# sonoff_DIY_3_gang_Smd_version-V_1_3.net
KiCad netlist of a schematic drawn in EAGLE
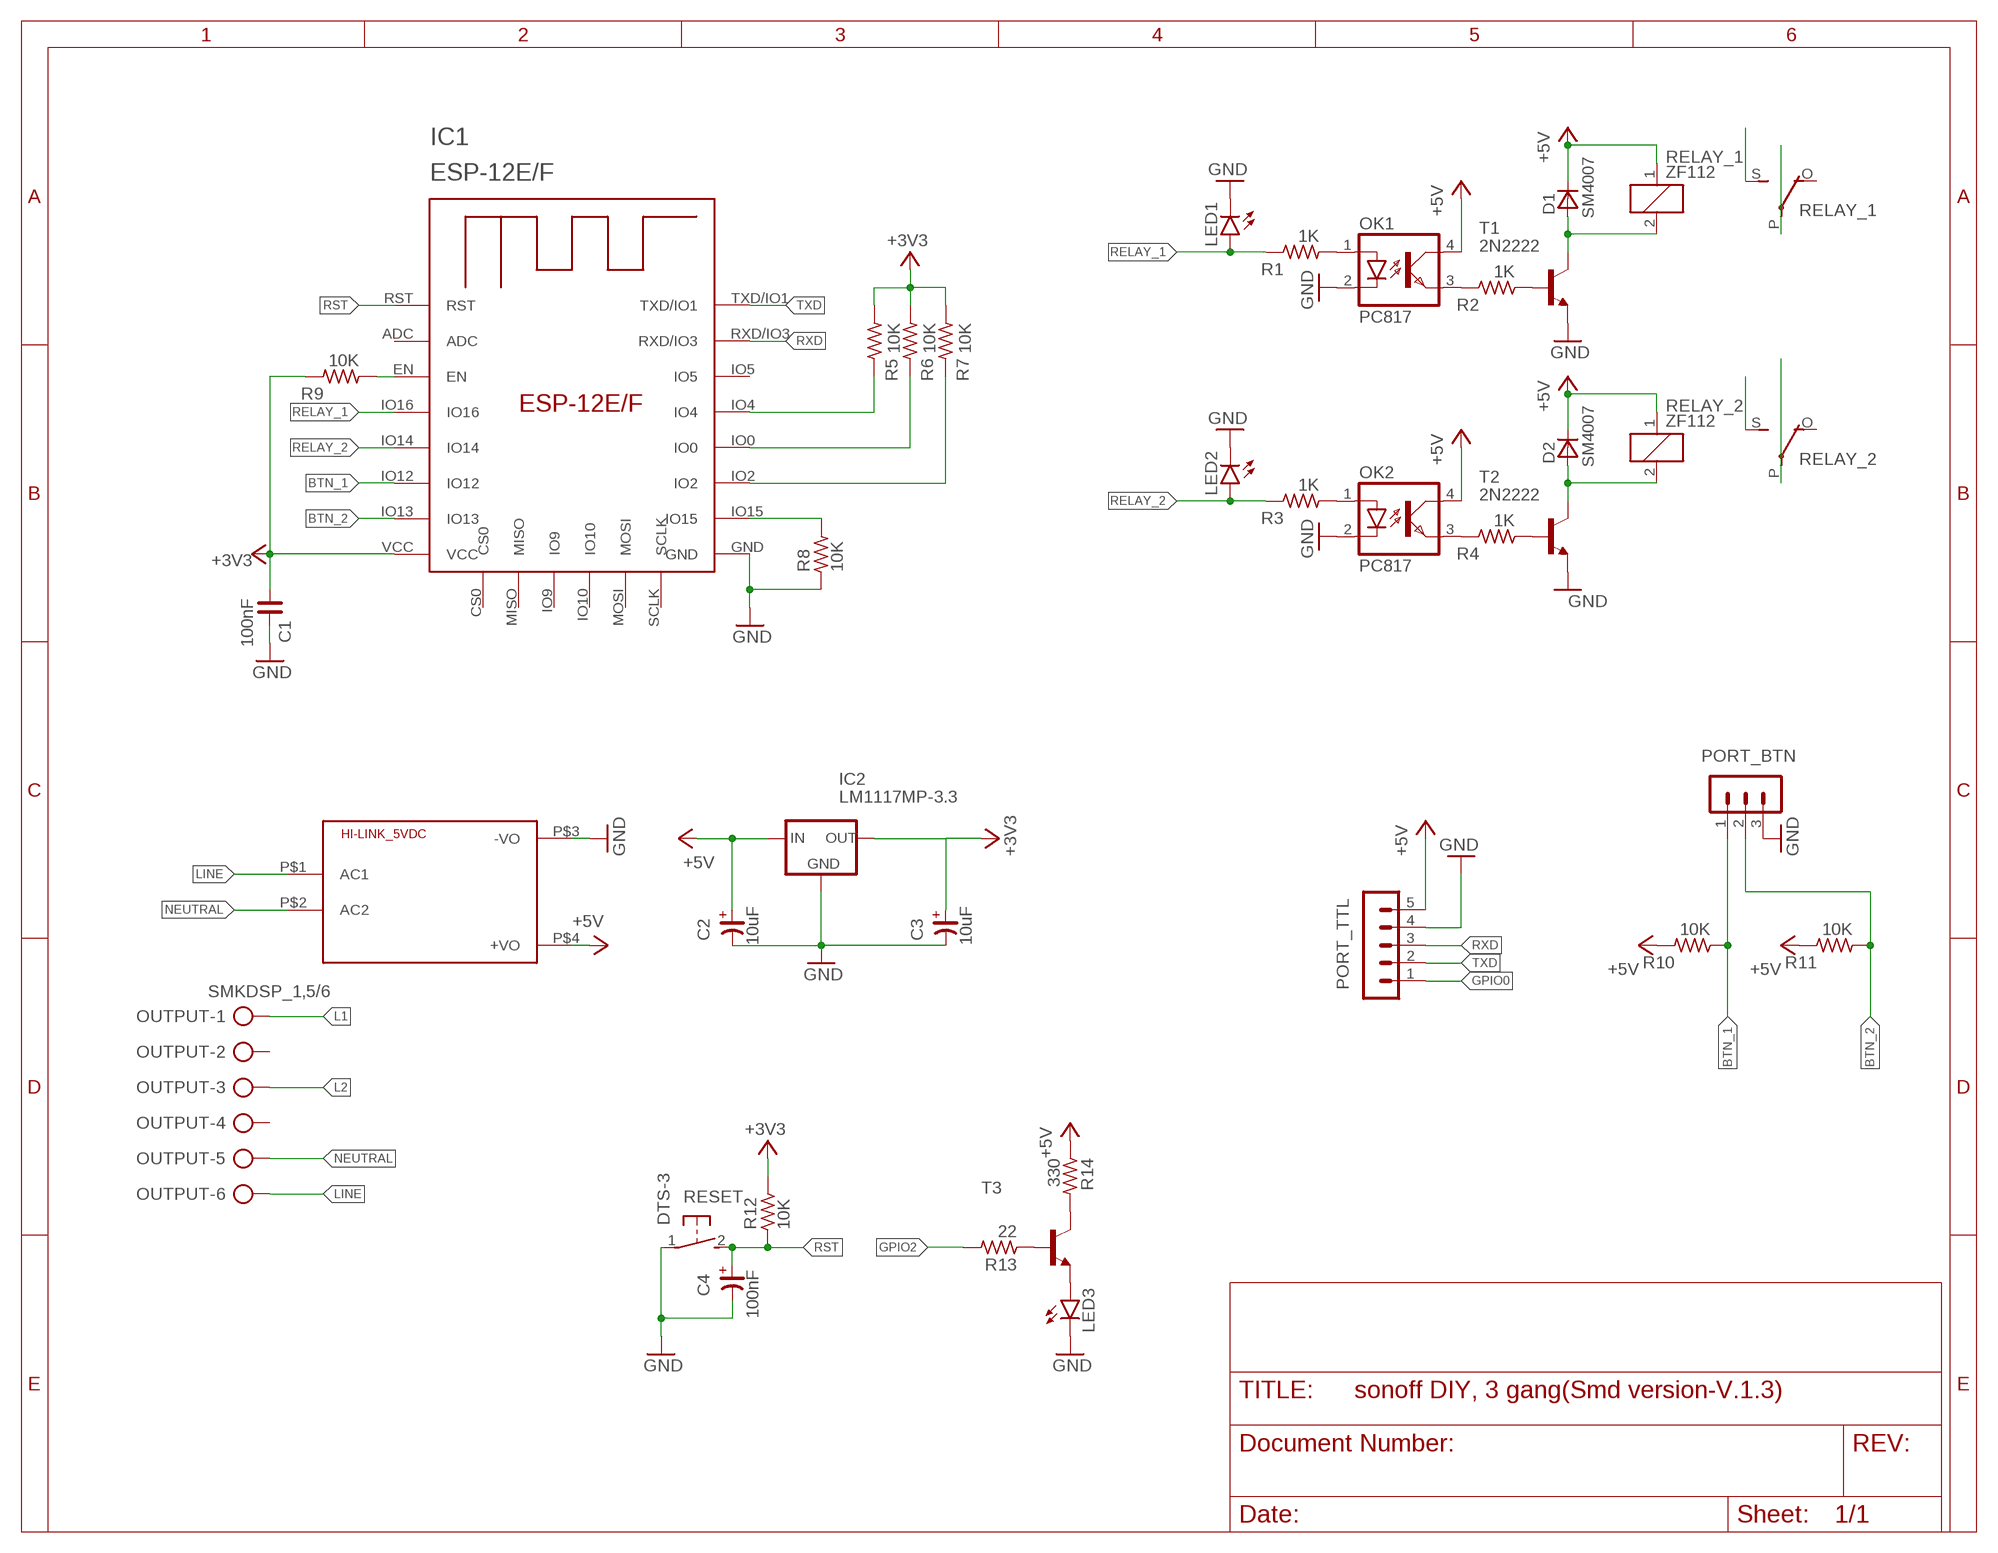
[diagram p0: schematic, sheet 1]

(export (version "E")
  (design (tool "Eeschema 10.0.6"))
  (components
    (comp (ref "C1")
      (value "100nF")
      (footprint "eagle-import:C0805")
      (libsource (lib "eagle-import") (part "C_0805"))
    )
    (comp (ref "C2")
      (value "10uF")
      (footprint "eagle-import:C3528_T")
      (libsource (lib "eagle-import") (part "CP_3528"))
    )
    (comp (ref "C3")
      (value "10uF")
      (footprint "eagle-import:C3528_T")
      (libsource (lib "eagle-import") (part "CP_3528"))
    )
    (comp (ref "C4")
      (value "100nF")
      (footprint "eagle-import:C3528_T")
      (libsource (lib "eagle-import") (part "CP_3528"))
    )
    (comp (ref "D1")
      (value "SM4007")
      (footprint "eagle-import:MELF-MLL41")
      (libsource (lib "eagle-import") (part "SM4007"))
    )
    (comp (ref "D2")
      (value "SM4007")
      (footprint "eagle-import:MELF-MLL41")
      (libsource (lib "eagle-import") (part "SM4007"))
    )
    (comp (ref "HI-LINK_5VDC")
      (value "HLK-PM013W")
      (footprint "eagle-import:HLK-PM01")
      (libsource (lib "eagle-import") (part "HLK-PM013W"))
    )
    (comp (ref "IC1")
      (value "ESP-12E/F")
      (footprint "eagle-import:ESP-12E")
      (libsource (lib "eagle-import") (part "ESP-12E/F"))
    )
    (comp (ref "IC2")
      (value "LM1117MP-3.3")
      (footprint "eagle-import:SOT223")
      (fields (field (name "MF") "Texas Instruments"))
      (libsource (lib "eagle-import") (part "LM1117?-MP3.3"))
    )
    (comp (ref "LED1")
      (value "LED3MM")
      (footprint "eagle-import:LED3MM")
      (libsource (lib "eagle-import") (part "LED3MM"))
    )
    (comp (ref "LED2")
      (value "LED3MM")
      (footprint "eagle-import:LED3MM")
      (libsource (lib "eagle-import") (part "LED3MM"))
    )
    (comp (ref "LED3")
      (value "LED3MM")
      (footprint "eagle-import:LED3MM")
      (libsource (lib "eagle-import") (part "LED3MM"))
    )
    (comp (ref "OK1")
      (value "PC817")
      (footprint "eagle-import:DIL04")
      (fields (field (name "MPN") "PC817X4J000F"))
      (libsource (lib "eagle-import") (part "PC817"))
    )
    (comp (ref "OK2")
      (value "PC817")
      (footprint "eagle-import:DIL04")
      (fields (field (name "MPN") "PC817X4J000F"))
      (libsource (lib "eagle-import") (part "PC817"))
    )
    (comp (ref "OUTPUT")
      (value "SMKDSP_1,5/6")
      (footprint "eagle-import:SMKDSP_1,5_6")
      (fields (field (name "MF") "FARNELL") (field (name "MPN") "1733619"))
      (libsource (lib "eagle-import") (part "SMKDSP_1,5/6"))
    )
    (comp (ref "PORT_BTN")
      (value "MA03-1")
      (footprint "eagle-import:MA03-1")
      (libsource (lib "eagle-import") (part "MA03-1"))
    )
    (comp (ref "PORT_TTL")
      (value "MA05-1")
      (footprint "eagle-import:MA05-1")
      (libsource (lib "eagle-import") (part "MA05-1"))
    )
    (comp (ref "R1")
      (value "1K")
      (footprint "eagle-import:R0805")
      (libsource (lib "eagle-import") (part "R_0805"))
    )
    (comp (ref "R2")
      (value "1K")
      (footprint "eagle-import:R0805")
      (libsource (lib "eagle-import") (part "R_0805"))
    )
    (comp (ref "R3")
      (value "1K")
      (footprint "eagle-import:R0805")
      (libsource (lib "eagle-import") (part "R_0805"))
    )
    (comp (ref "R4")
      (value "1K")
      (footprint "eagle-import:R0805")
      (libsource (lib "eagle-import") (part "R_0805"))
    )
    (comp (ref "R5")
      (value "10K")
      (footprint "eagle-import:R0805")
      (libsource (lib "eagle-import") (part "R_0805"))
    )
    (comp (ref "R6")
      (value "10K")
      (footprint "eagle-import:R0805")
      (libsource (lib "eagle-import") (part "R_0805"))
    )
    (comp (ref "R7")
      (value "10K")
      (footprint "eagle-import:R0805")
      (libsource (lib "eagle-import") (part "R_0805"))
    )
    (comp (ref "R8")
      (value "10K")
      (footprint "eagle-import:R0805")
      (libsource (lib "eagle-import") (part "R_0805"))
    )
    (comp (ref "R9")
      (value "10K")
      (footprint "eagle-import:R0805")
      (libsource (lib "eagle-import") (part "R_0805"))
    )
    (comp (ref "R10")
      (value "10K")
      (footprint "eagle-import:R0805")
      (libsource (lib "eagle-import") (part "R_0805"))
    )
    (comp (ref "R11")
      (value "10K")
      (footprint "eagle-import:R0805")
      (libsource (lib "eagle-import") (part "R_0805"))
    )
    (comp (ref "R12")
      (value "10K")
      (footprint "eagle-import:R0805")
      (libsource (lib "eagle-import") (part "R_0805"))
    )
    (comp (ref "R13")
      (value "22")
      (footprint "eagle-import:R0805")
      (libsource (lib "eagle-import") (part "R_0805"))
    )
    (comp (ref "R14")
      (value "330")
      (footprint "eagle-import:R0805")
      (libsource (lib "eagle-import") (part "R_0805"))
    )
    (comp (ref "RELAY_1")
      (value "ZF112")
      (footprint "eagle-import:ZF112")
      (libsource (lib "eagle-import") (part "ZF112"))
    )
    (comp (ref "RELAY_2")
      (value "ZF112")
      (footprint "eagle-import:ZF112")
      (libsource (lib "eagle-import") (part "ZF112"))
    )
    (comp (ref "RESET")
      (value "DTS-3")
      (footprint "eagle-import:DTS-3")
      (libsource (lib "eagle-import") (part "DTS-3"))
    )
    (comp (ref "T1")
      (value "2N2222")
      (footprint "eagle-import:TO18")
      (libsource (lib "eagle-import") (part "2N2222"))
    )
    (comp (ref "T2")
      (value "2N2222")
      (footprint "eagle-import:TO18")
      (libsource (lib "eagle-import") (part "2N2222"))
    )
    (comp (ref "T3")
      (value "BC817-16LT1-NPN-SOT23-BEC")
      (footprint "eagle-import:SOT23-BEC")
      (libsource (lib "eagle-import") (part "-NPN-SOT23-BECBC817-16LT1"))
    )
  )
  (nets
    (net (code "1") (name "+3V3") (class "Default")
      (node (ref "C1") (pin "1") (pinfunction "1_1") (pintype "passive"))
      (node (ref "C3") (pin "+") (pinfunction "+_+") (pintype "passive"))
      (node (ref "IC1") (pin "VCC") (pinfunction "VCC_VCC") (pintype "power_in"))
      (node (ref "IC2") (pin "2") (pinfunction "OUT_2") (pintype "passive"))
      (node (ref "IC2") (pin "4") (pinfunction "OUT_4") (pintype "passive"))
      (node (ref "R12") (pin "2") (pinfunction "2_2") (pintype "passive"))
      (node (ref "R5") (pin "1") (pinfunction "1_1") (pintype "passive"))
      (node (ref "R6") (pin "1") (pinfunction "1_1") (pintype "passive"))
      (node (ref "R7") (pin "1") (pinfunction "1_1") (pintype "passive"))
      (node (ref "R9") (pin "2") (pinfunction "2_2") (pintype "passive"))
    )
    (net (code "2") (name "+5V") (class "Default")
      (node (ref "C2") (pin "+") (pinfunction "+_+") (pintype "passive"))
      (node (ref "D1") (pin "C") (pinfunction "C_C") (pintype "passive"))
      (node (ref "D2") (pin "C") (pinfunction "C_C") (pintype "passive"))
      (node (ref "HI-LINK_5VDC") (pin "P$4") (pinfunction "+VO_P$4") (pintype "bidirectional"))
      (node (ref "IC2") (pin "3") (pinfunction "IN_3") (pintype "input"))
      (node (ref "OK1") (pin "4") (pinfunction "COL_4") (pintype "passive"))
      (node (ref "OK2") (pin "4") (pinfunction "COL_4") (pintype "passive"))
      (node (ref "PORT_TTL") (pin "5") (pinfunction "5_5") (pintype "passive"))
      (node (ref "R10") (pin "2") (pinfunction "2_2") (pintype "passive"))
      (node (ref "R11") (pin "2") (pinfunction "2_2") (pintype "passive"))
      (node (ref "R14") (pin "1") (pinfunction "1_1") (pintype "passive"))
      (node (ref "RELAY_1") (pin "1") (pinfunction "1_1") (pintype "passive"))
      (node (ref "RELAY_2") (pin "1") (pinfunction "1_1") (pintype "passive"))
    )
    (net (code "3") (name "BTN_1") (class "Default")
      (node (ref "IC1") (pin "IO12") (pinfunction "IO12_IO12") (pintype "bidirectional"))
      (node (ref "PORT_BTN") (pin "1") (pinfunction "1_1") (pintype "passive"))
      (node (ref "R10") (pin "1") (pinfunction "1_1") (pintype "passive"))
    )
    (net (code "4") (name "BTN_2") (class "Default")
      (node (ref "IC1") (pin "IO13") (pinfunction "IO13_IO13") (pintype "bidirectional"))
      (node (ref "PORT_BTN") (pin "2") (pinfunction "2_2") (pintype "passive"))
      (node (ref "R11") (pin "1") (pinfunction "1_1") (pintype "passive"))
    )
    (net (code "5") (name "GND") (class "Default")
      (node (ref "C1") (pin "2") (pinfunction "2_2") (pintype "passive"))
      (node (ref "C2") (pin "-") (pinfunction "-_-") (pintype "passive"))
      (node (ref "C3") (pin "-") (pinfunction "-_-") (pintype "passive"))
      (node (ref "C4") (pin "-") (pinfunction "-_-") (pintype "passive"))
      (node (ref "HI-LINK_5VDC") (pin "P$3") (pinfunction "-VO_P$3") (pintype "bidirectional"))
      (node (ref "IC1") (pin "GND") (pinfunction "GND_GND") (pintype "power_in"))
      (node (ref "IC2") (pin "1") (pinfunction "GND_1") (pintype "input"))
      (node (ref "LED1") (pin "K") (pinfunction "C_K") (pintype "passive"))
      (node (ref "LED2") (pin "K") (pinfunction "C_K") (pintype "passive"))
      (node (ref "LED3") (pin "K") (pinfunction "C_K") (pintype "passive"))
      (node (ref "OK1") (pin "2") (pinfunction "C_2") (pintype "passive"))
      (node (ref "OK2") (pin "2") (pinfunction "C_2") (pintype "passive"))
      (node (ref "PORT_BTN") (pin "3") (pinfunction "3_3") (pintype "passive"))
      (node (ref "PORT_TTL") (pin "4") (pinfunction "4_4") (pintype "passive"))
      (node (ref "R8") (pin "1") (pinfunction "1_1") (pintype "passive"))
      (node (ref "RESET") (pin "1") (pinfunction "1_1") (pintype "passive"))
      (node (ref "T1") (pin "1") (pinfunction "E_1") (pintype "passive"))
      (node (ref "T2") (pin "1") (pinfunction "E_1") (pintype "passive"))
    )
    (net (code "6") (name "GPIO0") (class "Default")
      (node (ref "IC1") (pin "IO0") (pinfunction "IO0_IO0") (pintype "bidirectional"))
      (node (ref "PORT_TTL") (pin "1") (pinfunction "1_1") (pintype "passive"))
      (node (ref "R6") (pin "2") (pinfunction "2_2") (pintype "passive"))
    )
    (net (code "7") (name "GPIO2") (class "Default")
      (node (ref "IC1") (pin "IO2") (pinfunction "IO2_IO2") (pintype "bidirectional"))
      (node (ref "R13") (pin "2") (pinfunction "2_2") (pintype "passive"))
      (node (ref "R7") (pin "2") (pinfunction "2_2") (pintype "passive"))
    )
    (net (code "8") (name "L1") (class "Default")
      (node (ref "OUTPUT") (pin "1") (pinfunction "KL_1") (pintype "passive"))
      (node (ref "RELAY_1") (pin "S") (pinfunction "S_S") (pintype "passive"))
    )
    (net (code "9") (name "L2") (class "Default")
      (node (ref "OUTPUT") (pin "3") (pinfunction "KL_3") (pintype "passive"))
      (node (ref "RELAY_2") (pin "S") (pinfunction "S_S") (pintype "passive"))
    )
    (net (code "10") (name "LINE") (class "Default")
      (node (ref "HI-LINK_5VDC") (pin "P$1") (pinfunction "AC1_P$1") (pintype "bidirectional"))
      (node (ref "OUTPUT") (pin "6") (pinfunction "KL_6") (pintype "passive"))
      (node (ref "RELAY_1") (pin "P") (pinfunction "P_P") (pintype "passive"))
      (node (ref "RELAY_2") (pin "P") (pinfunction "P_P") (pintype "passive"))
    )
    (net (code "11") (name "NEUTRAL") (class "Default")
      (node (ref "HI-LINK_5VDC") (pin "P$2") (pinfunction "AC2_P$2") (pintype "bidirectional"))
      (node (ref "OUTPUT") (pin "5") (pinfunction "KL_5") (pintype "passive"))
    )
    (net (code "12") (name "Net-(IC1-PadEN)") (class "Default")
      (node (ref "IC1") (pin "EN") (pinfunction "EN_EN") (pintype "bidirectional"))
      (node (ref "R9") (pin "1") (pinfunction "1_1") (pintype "passive"))
    )
    (net (code "13") (name "Net-(IC1-PadIO4)") (class "Default")
      (node (ref "IC1") (pin "IO4") (pinfunction "IO4_IO4") (pintype "bidirectional"))
      (node (ref "R5") (pin "2") (pinfunction "2_2") (pintype "passive"))
    )
    (net (code "14") (name "Net-(IC1-PadIO15)") (class "Default")
      (node (ref "IC1") (pin "IO15") (pinfunction "IO15_IO15") (pintype "bidirectional"))
      (node (ref "R8") (pin "2") (pinfunction "2_2") (pintype "passive"))
    )
    (net (code "15") (name "Net-(LED3-PadA)") (class "Default")
      (node (ref "LED3") (pin "A") (pinfunction "A_A") (pintype "passive"))
      (node (ref "T3") (pin "E") (pinfunction "E_E") (pintype "passive"))
    )
    (net (code "16") (name "Net-(OK1-A)") (class "Default")
      (node (ref "OK1") (pin "1") (pinfunction "A_1") (pintype "passive"))
      (node (ref "R1") (pin "1") (pinfunction "1_1") (pintype "passive"))
    )
    (net (code "17") (name "Net-(OK1-EMIT)") (class "Default")
      (node (ref "OK1") (pin "3") (pinfunction "EMIT_3") (pintype "passive"))
      (node (ref "R2") (pin "2") (pinfunction "2_2") (pintype "passive"))
    )
    (net (code "18") (name "Net-(OK2-A)") (class "Default")
      (node (ref "OK2") (pin "1") (pinfunction "A_1") (pintype "passive"))
      (node (ref "R3") (pin "1") (pinfunction "1_1") (pintype "passive"))
    )
    (net (code "19") (name "Net-(OK2-EMIT)") (class "Default")
      (node (ref "OK2") (pin "3") (pinfunction "EMIT_3") (pintype "passive"))
      (node (ref "R4") (pin "2") (pinfunction "2_2") (pintype "passive"))
    )
    (net (code "20") (name "Net-(R13-Pad1)") (class "Default")
      (node (ref "R13") (pin "1") (pinfunction "1_1") (pintype "passive"))
      (node (ref "T3") (pin "B") (pinfunction "B_B") (pintype "passive"))
    )
    (net (code "21") (name "Net-(R14-Pad2)") (class "Default")
      (node (ref "R14") (pin "2") (pinfunction "2_2") (pintype "passive"))
      (node (ref "T3") (pin "C") (pinfunction "C_C") (pintype "passive"))
    )
    (net (code "22") (name "Net-(T1-B)") (class "Default")
      (node (ref "R2") (pin "1") (pinfunction "1_1") (pintype "passive"))
      (node (ref "T1") (pin "2") (pinfunction "B_2") (pintype "passive"))
    )
    (net (code "23") (name "Net-(T1-C)") (class "Default")
      (node (ref "D1") (pin "A") (pinfunction "A_A") (pintype "passive"))
      (node (ref "RELAY_1") (pin "2") (pinfunction "2_2") (pintype "passive"))
      (node (ref "T1") (pin "3") (pinfunction "C_3") (pintype "passive"))
    )
    (net (code "24") (name "Net-(T2-B)") (class "Default")
      (node (ref "R4") (pin "1") (pinfunction "1_1") (pintype "passive"))
      (node (ref "T2") (pin "2") (pinfunction "B_2") (pintype "passive"))
    )
    (net (code "25") (name "Net-(T2-C)") (class "Default")
      (node (ref "D2") (pin "A") (pinfunction "A_A") (pintype "passive"))
      (node (ref "RELAY_2") (pin "2") (pinfunction "2_2") (pintype "passive"))
      (node (ref "T2") (pin "3") (pinfunction "C_3") (pintype "passive"))
    )
    (net (code "26") (name "RELAY_1") (class "Default")
      (node (ref "IC1") (pin "IO16") (pinfunction "IO16_IO16") (pintype "bidirectional"))
      (node (ref "LED1") (pin "A") (pinfunction "A_A") (pintype "passive"))
      (node (ref "R1") (pin "2") (pinfunction "2_2") (pintype "passive"))
    )
    (net (code "27") (name "RELAY_2") (class "Default")
      (node (ref "IC1") (pin "IO14") (pinfunction "IO14_IO14") (pintype "bidirectional"))
      (node (ref "LED2") (pin "A") (pinfunction "A_A") (pintype "passive"))
      (node (ref "R3") (pin "2") (pinfunction "2_2") (pintype "passive"))
    )
    (net (code "28") (name "RST") (class "Default")
      (node (ref "C4") (pin "+") (pinfunction "+_+") (pintype "passive"))
      (node (ref "IC1") (pin "RST") (pinfunction "RST_RST") (pintype "input"))
      (node (ref "R12") (pin "1") (pinfunction "1_1") (pintype "passive"))
      (node (ref "RESET") (pin "2") (pinfunction "2_2") (pintype "passive"))
    )
    (net (code "29") (name "RXD") (class "Default")
      (node (ref "IC1") (pin "RXD/IO3") (pinfunction "RXD/IO3_RXD/IO3") (pintype "bidirectional"))
      (node (ref "PORT_TTL") (pin "3") (pinfunction "3_3") (pintype "passive"))
    )
    (net (code "30") (name "TXD") (class "Default")
      (node (ref "IC1") (pin "TXD/IO1") (pinfunction "TXD/IO1_TXD/IO1") (pintype "bidirectional"))
      (node (ref "PORT_TTL") (pin "2") (pinfunction "2_2") (pintype "passive"))
    )
    (net (code "31") (name "unconnected-(IC1-PadADC)") (class "Default")
      (node (ref "IC1") (pin "ADC") (pinfunction "ADC_ADC") (pintype "bidirectional"))
    )
    (net (code "32") (name "unconnected-(IC1-PadCS0)") (class "Default")
      (node (ref "IC1") (pin "CS0") (pinfunction "CS0_CS0") (pintype "bidirectional"))
    )
    (net (code "33") (name "unconnected-(IC1-PadIO5)") (class "Default")
      (node (ref "IC1") (pin "IO5") (pinfunction "IO5_IO5") (pintype "bidirectional"))
    )
    (net (code "34") (name "unconnected-(IC1-PadIO9)") (class "Default")
      (node (ref "IC1") (pin "IO9") (pinfunction "IO9_IO9") (pintype "bidirectional"))
    )
    (net (code "35") (name "unconnected-(IC1-PadIO10)") (class "Default")
      (node (ref "IC1") (pin "IO10") (pinfunction "IO10_IO10") (pintype "bidirectional"))
    )
    (net (code "36") (name "unconnected-(IC1-PadMISO)") (class "Default")
      (node (ref "IC1") (pin "MISO") (pinfunction "MISO_MISO") (pintype "bidirectional"))
    )
    (net (code "37") (name "unconnected-(IC1-PadMOSI)") (class "Default")
      (node (ref "IC1") (pin "MOSI") (pinfunction "MOSI_MOSI") (pintype "bidirectional"))
    )
    (net (code "38") (name "unconnected-(IC1-PadSCLK)") (class "Default")
      (node (ref "IC1") (pin "SCLK") (pinfunction "SCLK_SCLK") (pintype "bidirectional"))
    )
    (net (code "39") (name "unconnected-(OUTPUTB-KL-Pad2)") (class "Default")
      (node (ref "OUTPUT") (pin "2") (pinfunction "KL_2") (pintype "passive"))
    )
    (net (code "40") (name "unconnected-(OUTPUTD-KL-Pad4)") (class "Default")
      (node (ref "OUTPUT") (pin "4") (pinfunction "KL_4") (pintype "passive"))
    )
    (net (code "41") (name "unconnected-(RELAY_1-PadO)") (class "Default")
      (node (ref "RELAY_1") (pin "O") (pinfunction "O_O") (pintype "passive"))
    )
    (net (code "42") (name "unconnected-(RELAY_2-PadO)") (class "Default")
      (node (ref "RELAY_2") (pin "O") (pinfunction "O_O") (pintype "passive"))
    )
  )
)
